# LooSensorNodeV2.net
KiCad netlist of a schematic drawn in EAGLE
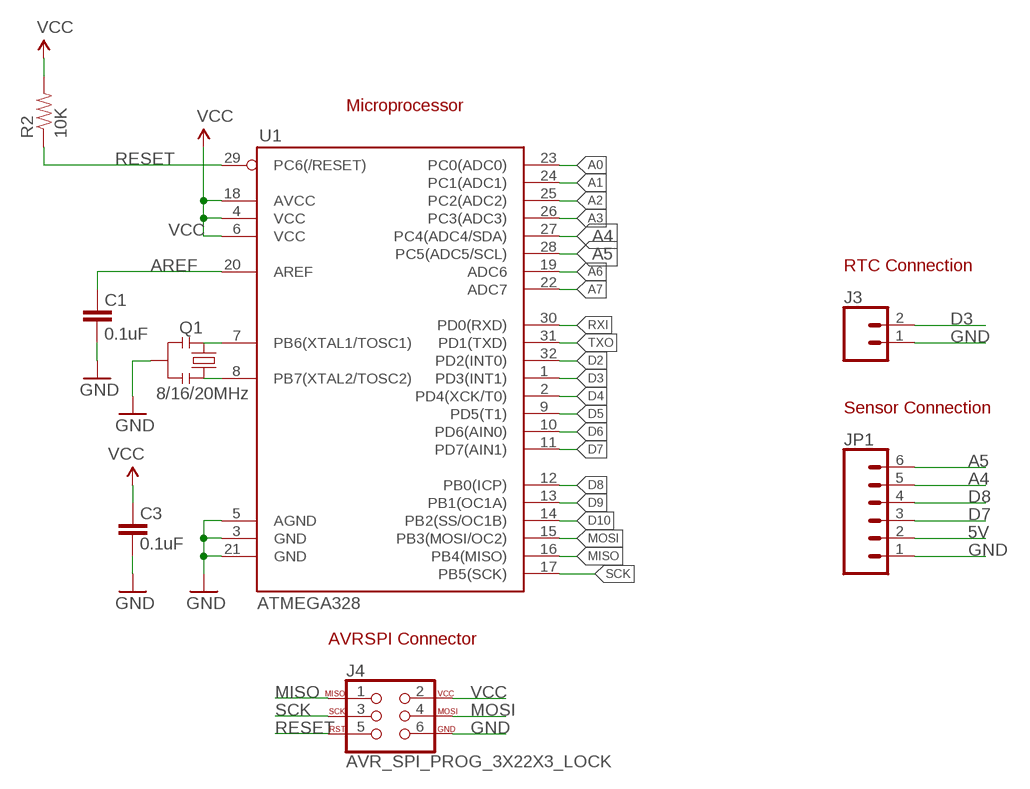
[diagram p0: schematic, sheet 1]
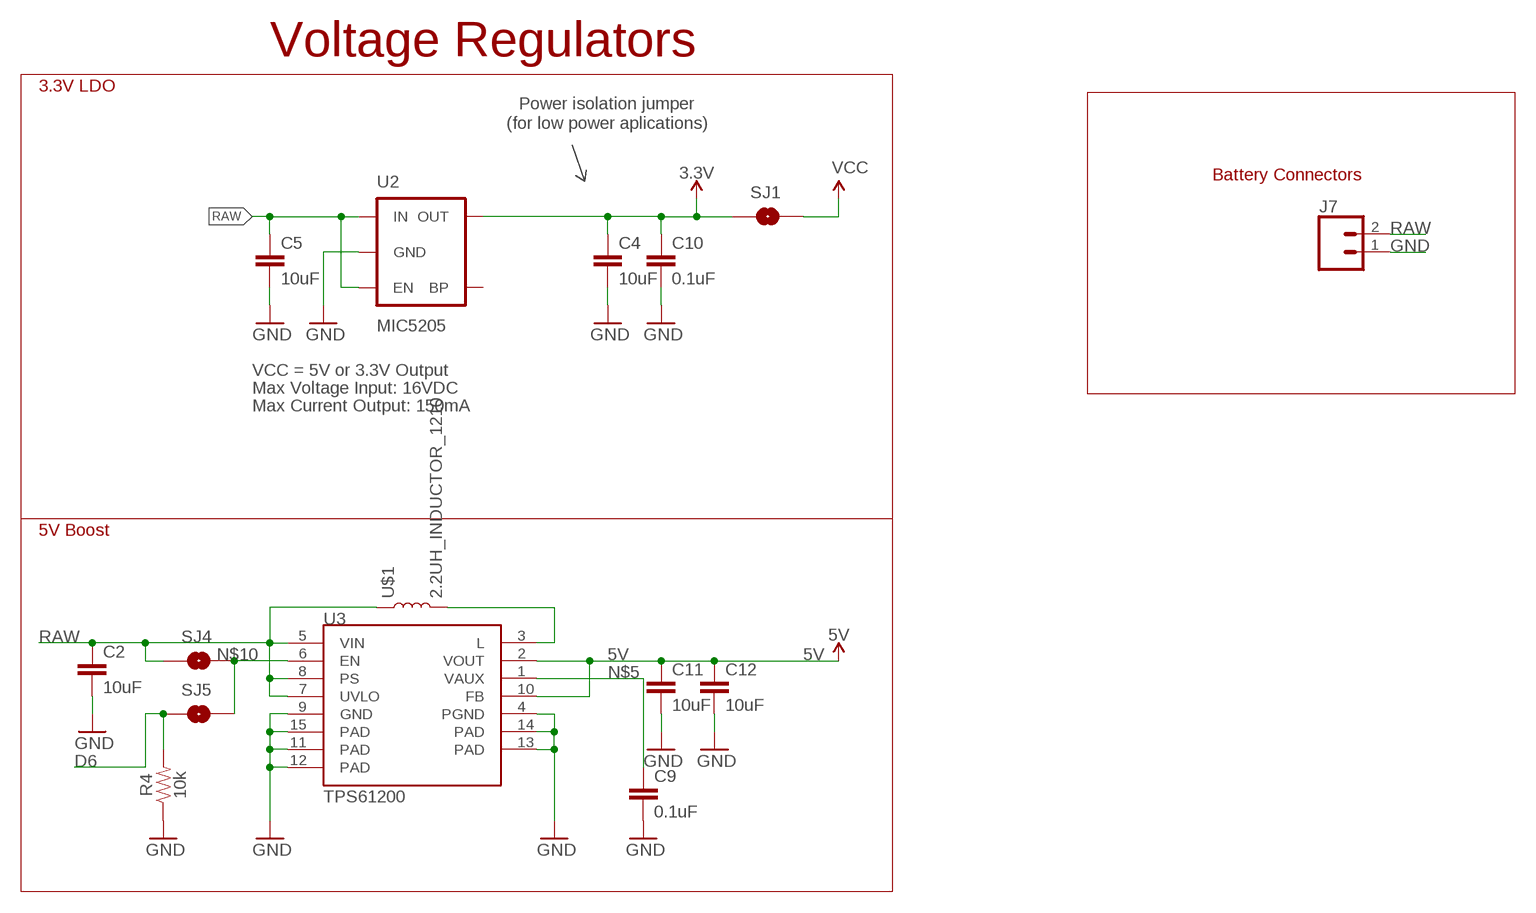
[diagram p1: schematic, sheet 2]
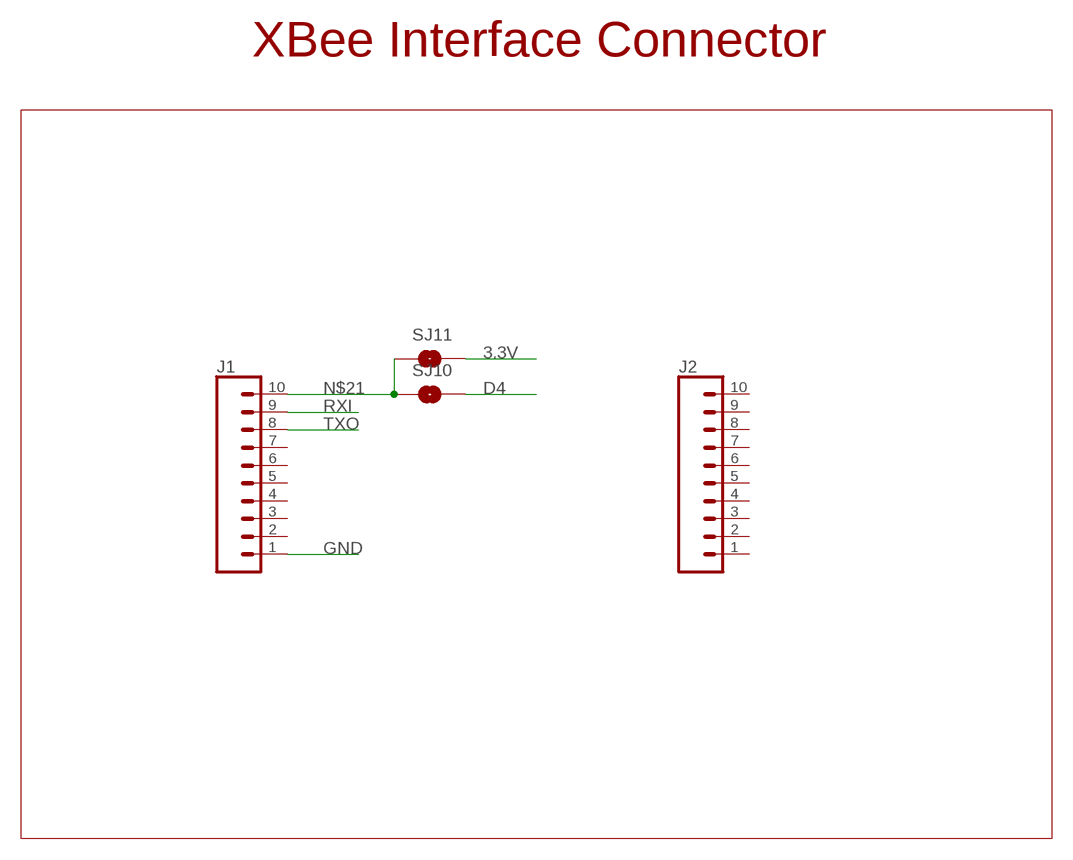
[diagram p2: schematic, sheet 3]

(export (version "E")
  (design (tool "Eeschema 10.0.6"))
  (components
    (comp (ref "C2")
      (value "10uF")
      (footprint "eagle-import:0603")
      (libsource (lib "eagle-import") (part "10UF-0603-6.3V-20%"))
    )
    (comp (ref "C4")
      (value "10uF")
      (footprint "eagle-import:0603")
      (libsource (lib "eagle-import") (part "10UF-0603-6.3V-20%"))
    )
    (comp (ref "C5")
      (value "10uF")
      (footprint "eagle-import:0603")
      (libsource (lib "eagle-import") (part "10UF-0603-6.3V-20%"))
    )
    (comp (ref "C9")
      (value "0.1uF")
      (footprint "eagle-import:0603")
      (libsource (lib "eagle-import") (part "0.1UF-0603-25V-5%"))
    )
    (comp (ref "C10")
      (value "0.1uF")
      (footprint "eagle-import:0603-CAP")
      (libsource (lib "eagle-import") (part "CAP0603-CAP"))
    )
    (comp (ref "C11")
      (value "10uF")
      (footprint "eagle-import:0603")
      (libsource (lib "eagle-import") (part "10UF-0603-6.3V-20%"))
    )
    (comp (ref "C12")
      (value "10uF")
      (footprint "eagle-import:0603")
      (libsource (lib "eagle-import") (part "10UF-0603-6.3V-20%"))
    )
    (comp (ref "J7")
      (value "CONN_02")
      (footprint "eagle-import:1X02")
      (libsource (lib "eagle-import") (part "CONN_02"))
    )
    (comp (ref "R4")
      (value "10k")
      (footprint "eagle-import:0603")
      (libsource (lib "eagle-import") (part "10KOHM-0603-1/10W-1%"))
    )
    (comp (ref "SJ1")
      (value "SOLDERJUMPERNC")
      (footprint "eagle-import:SJ_2S")
      (libsource (lib "eagle-import") (part "SOLDERJUMPERNC"))
    )
    (comp (ref "SJ4")
      (value "SOLDERJUMPERNC")
      (footprint "eagle-import:SJ_2S")
      (libsource (lib "eagle-import") (part "SOLDERJUMPERNC"))
    )
    (comp (ref "SJ5")
      (value "SOLDERJUMPERNC")
      (footprint "eagle-import:SJ_2S")
      (libsource (lib "eagle-import") (part "SOLDERJUMPERNC"))
    )
    (comp (ref "U$1")
      (value "2.2UH_INDUCTOR_1210")
      (footprint "eagle-import:1210")
      (libsource (lib "eagle-import") (part "2.2UH_INDUCTOR_1210"))
    )
    (comp (ref "U2")
      (value "MIC5205")
      (footprint "eagle-import:SOT23-5")
      (libsource (lib "eagle-import") (part "V_REG_LDOSMD"))
    )
    (comp (ref "U3")
      (value "TPS61200")
      (footprint "eagle-import:QFN-10_PAD")
      (libsource (lib "eagle-import") (part "TPS61200"))
    )
    (comp (ref "C1")
      (value "0.1uF")
      (footprint "eagle-import:0603-CAP")
      (libsource (lib "eagle-import") (part "CAP0603-CAP"))
    )
    (comp (ref "C3")
      (value "0.1uF")
      (footprint "eagle-import:0603-CAP")
      (libsource (lib "eagle-import") (part "CAP0603-CAP"))
    )
    (comp (ref "J3")
      (value "CONN_02")
      (footprint "eagle-import:1X02")
      (libsource (lib "eagle-import") (part "CONN_02"))
    )
    (comp (ref "J4")
      (value "AVR_SPI_PROG_3X22X3_LOCK")
      (footprint "eagle-import:2X3_LOCK")
      (libsource (lib "eagle-import") (part "AVR_SPI_PROG_3X22X3_LOCK"))
    )
    (comp (ref "JP1")
      (value "CONN_06SILK_FEMALE_PTH")
      (footprint "eagle-import:1X06")
      (libsource (lib "eagle-import") (part "CONN_06SILK_FEMALE_PTH"))
    )
    (comp (ref "Q1")
      (value "8/16/20MHz")
      (footprint "eagle-import:RESONATOR-SMD-1_1")
      (libsource (lib "eagle-import") (part "RESONATOR1{colon}1"))
    )
    (comp (ref "R2")
      (value "10K")
      (footprint "eagle-import:0603-RES")
      (libsource (lib "eagle-import") (part "RESISTOR0603-RES"))
    )
    (comp (ref "U1")
      (value "ATMEGA328")
      (footprint "eagle-import:TQFP32-08")
      (libsource (lib "eagle-import") (part "ATMEGA168"))
    )
    (comp (ref "J1")
      (value "CONN_102MM")
      (footprint "eagle-import:1X10-2MM")
      (libsource (lib "eagle-import") (part "CONN_102MM"))
    )
    (comp (ref "J2")
      (value "CONN_102MM")
      (footprint "eagle-import:1X10-2MM")
      (libsource (lib "eagle-import") (part "CONN_102MM"))
    )
    (comp (ref "SJ10")
      (value "SOLDERJUMPERNC")
      (footprint "eagle-import:SJ_2S")
      (libsource (lib "eagle-import") (part "SOLDERJUMPERNC"))
    )
    (comp (ref "SJ11")
      (value "SOLDERJUMPERNC")
      (footprint "eagle-import:SJ_2S")
      (libsource (lib "eagle-import") (part "SOLDERJUMPERNC"))
    )
  )
  (nets
    (net (code "1") (name "3.3V") (class "Default")
      (node (ref "C10") (pin "1") (pinfunction "1_1") (pintype "passive"))
      (node (ref "C4") (pin "1") (pinfunction "1_1") (pintype "passive"))
      (node (ref "SJ1") (pin "1") (pinfunction "1_1") (pintype "passive"))
      (node (ref "SJ11") (pin "2") (pinfunction "2_2") (pintype "passive"))
      (node (ref "U2") (pin "5") (pinfunction "OUT_5") (pintype "passive"))
    )
    (net (code "2") (name "5V") (class "Default")
      (node (ref "C11") (pin "1") (pinfunction "1_1") (pintype "passive"))
      (node (ref "C12") (pin "1") (pinfunction "1_1") (pintype "passive"))
      (node (ref "JP1") (pin "2") (pinfunction "2_2") (pintype "passive"))
      (node (ref "U3") (pin "10") (pinfunction "FB_10") (pintype "passive"))
      (node (ref "U3") (pin "2") (pinfunction "VOUT_2") (pintype "passive"))
    )
    (net (code "3") (name "A0") (class "Default")
      (node (ref "U1") (pin "23") (pinfunction "PC0(ADC0)_23") (pintype "bidirectional"))
    )
    (net (code "4") (name "A1") (class "Default")
      (node (ref "U1") (pin "24") (pinfunction "PC1(ADC1)_24") (pintype "bidirectional"))
    )
    (net (code "5") (name "A2") (class "Default")
      (node (ref "U1") (pin "25") (pinfunction "PC2(ADC2)_25") (pintype "bidirectional"))
    )
    (net (code "6") (name "A3") (class "Default")
      (node (ref "U1") (pin "26") (pinfunction "PC3(ADC3)_26") (pintype "bidirectional"))
    )
    (net (code "7") (name "A4") (class "Default")
      (node (ref "JP1") (pin "5") (pinfunction "5_5") (pintype "passive"))
      (node (ref "U1") (pin "27") (pinfunction "PC4(ADC4/SDA)_27") (pintype "bidirectional"))
    )
    (net (code "8") (name "A5") (class "Default")
      (node (ref "JP1") (pin "6") (pinfunction "6_6") (pintype "passive"))
      (node (ref "U1") (pin "28") (pinfunction "PC5(ADC5/SCL)_28") (pintype "bidirectional"))
    )
    (net (code "9") (name "A6") (class "Default")
      (node (ref "U1") (pin "19") (pinfunction "ADC6_19") (pintype "bidirectional"))
    )
    (net (code "10") (name "A7") (class "Default")
      (node (ref "U1") (pin "22") (pinfunction "ADC7_22") (pintype "bidirectional"))
    )
    (net (code "11") (name "AREF") (class "Default")
      (node (ref "C1") (pin "2") (pinfunction "2_2") (pintype "passive"))
      (node (ref "U1") (pin "20") (pinfunction "AREF_20") (pintype "bidirectional"))
    )
    (net (code "12") (name "D2") (class "Default")
      (node (ref "U1") (pin "32") (pinfunction "PD2(INT0)_32") (pintype "bidirectional"))
    )
    (net (code "13") (name "D3") (class "Default")
      (node (ref "J3") (pin "2") (pinfunction "2_2") (pintype "passive"))
      (node (ref "U1") (pin "1") (pinfunction "PD3(INT1)_1") (pintype "bidirectional"))
    )
    (net (code "14") (name "D4") (class "Default")
      (node (ref "SJ10") (pin "2") (pinfunction "2_2") (pintype "passive"))
      (node (ref "U1") (pin "2") (pinfunction "PD4(XCK/T0)_2") (pintype "bidirectional"))
    )
    (net (code "15") (name "D5") (class "Default")
      (node (ref "U1") (pin "9") (pinfunction "PD5(T1)_9") (pintype "bidirectional"))
    )
    (net (code "16") (name "D6") (class "Default")
      (node (ref "R4") (pin "2") (pinfunction "2_2") (pintype "passive"))
      (node (ref "SJ5") (pin "1") (pinfunction "1_1") (pintype "passive"))
      (node (ref "U1") (pin "10") (pinfunction "PD6(AIN0)_10") (pintype "bidirectional"))
    )
    (net (code "17") (name "D7") (class "Default")
      (node (ref "JP1") (pin "3") (pinfunction "3_3") (pintype "passive"))
      (node (ref "U1") (pin "11") (pinfunction "PD7(AIN1)_11") (pintype "bidirectional"))
    )
    (net (code "18") (name "D8") (class "Default")
      (node (ref "JP1") (pin "4") (pinfunction "4_4") (pintype "passive"))
      (node (ref "U1") (pin "12") (pinfunction "PB0(ICP)_12") (pintype "bidirectional"))
    )
    (net (code "19") (name "D9") (class "Default")
      (node (ref "U1") (pin "13") (pinfunction "PB1(OC1A)_13") (pintype "bidirectional"))
    )
    (net (code "20") (name "D10") (class "Default")
      (node (ref "U1") (pin "14") (pinfunction "PB2(SS/OC1B)_14") (pintype "bidirectional"))
    )
    (net (code "21") (name "GND") (class "Default")
      (node (ref "C1") (pin "1") (pinfunction "1_1") (pintype "passive"))
      (node (ref "C10") (pin "2") (pinfunction "2_2") (pintype "passive"))
      (node (ref "C11") (pin "2") (pinfunction "2_2") (pintype "passive"))
      (node (ref "C12") (pin "2") (pinfunction "2_2") (pintype "passive"))
      (node (ref "C2") (pin "2") (pinfunction "2_2") (pintype "passive"))
      (node (ref "C3") (pin "1") (pinfunction "1_1") (pintype "passive"))
      (node (ref "C4") (pin "2") (pinfunction "2_2") (pintype "passive"))
      (node (ref "C5") (pin "2") (pinfunction "2_2") (pintype "passive"))
      (node (ref "C9") (pin "2") (pinfunction "2_2") (pintype "passive"))
      (node (ref "J1") (pin "1") (pinfunction "1_1") (pintype "passive"))
      (node (ref "J3") (pin "1") (pinfunction "1_1") (pintype "passive"))
      (node (ref "J4") (pin "6") (pinfunction "6_6") (pintype "passive"))
      (node (ref "J7") (pin "1") (pinfunction "1_1") (pintype "passive"))
      (node (ref "JP1") (pin "1") (pinfunction "1_1") (pintype "passive"))
      (node (ref "Q1") (pin "2") (pinfunction "2_2") (pintype "passive"))
      (node (ref "R4") (pin "1") (pinfunction "1_1") (pintype "passive"))
      (node (ref "U1") (pin "21") (pinfunction "GND_21") (pintype "bidirectional"))
      (node (ref "U1") (pin "3") (pinfunction "GND_3") (pintype "bidirectional"))
      (node (ref "U1") (pin "5") (pinfunction "AGND_5") (pintype "bidirectional"))
      (node (ref "U2") (pin "2") (pinfunction "GND_2") (pintype "input"))
      (node (ref "U3") (pin "11") (pinfunction "PAD_11") (pintype "power_in"))
      (node (ref "U3") (pin "12") (pinfunction "PAD_12") (pintype "power_in"))
      (node (ref "U3") (pin "13") (pinfunction "PAD_13") (pintype "power_in"))
      (node (ref "U3") (pin "14") (pinfunction "PAD_14") (pintype "power_in"))
      (node (ref "U3") (pin "15") (pinfunction "PAD_15") (pintype "power_in"))
      (node (ref "U3") (pin "4") (pinfunction "PGND_4") (pintype "power_in"))
      (node (ref "U3") (pin "9") (pinfunction "GND_9") (pintype "power_in"))
    )
    (net (code "22") (name "MISO") (class "Default")
      (node (ref "J4") (pin "1") (pinfunction "1_1") (pintype "passive"))
      (node (ref "U1") (pin "16") (pinfunction "PB4(MISO)_16") (pintype "bidirectional"))
    )
    (net (code "23") (name "MOSI") (class "Default")
      (node (ref "J4") (pin "4") (pinfunction "4_4") (pintype "passive"))
      (node (ref "U1") (pin "15") (pinfunction "PB3(MOSI/OC2)_15") (pintype "bidirectional"))
    )
    (net (code "24") (name "N$5") (class "Default")
      (node (ref "C9") (pin "1") (pinfunction "1_1") (pintype "passive"))
      (node (ref "U3") (pin "1") (pinfunction "VAUX_1") (pintype "passive"))
    )
    (net (code "25") (name "N$10") (class "Default")
      (node (ref "SJ4") (pin "2") (pinfunction "2_2") (pintype "passive"))
      (node (ref "SJ5") (pin "2") (pinfunction "2_2") (pintype "passive"))
      (node (ref "U3") (pin "6") (pinfunction "EN_6") (pintype "input"))
    )
    (net (code "26") (name "N$21") (class "Default")
      (node (ref "J1") (pin "10") (pinfunction "10_10") (pintype "passive"))
      (node (ref "SJ10") (pin "1") (pinfunction "1_1") (pintype "passive"))
      (node (ref "SJ11") (pin "1") (pinfunction "1_1") (pintype "passive"))
    )
    (net (code "27") (name "Net-(U1-PB6(XTAL1{slash}TOSC1))") (class "Default")
      (node (ref "Q1") (pin "1") (pinfunction "1_1") (pintype "passive"))
      (node (ref "U1") (pin "7") (pinfunction "PB6(XTAL1/TOSC1)_7") (pintype "bidirectional"))
    )
    (net (code "28") (name "Net-(U1-PB7(XTAL2{slash}TOSC2))") (class "Default")
      (node (ref "Q1") (pin "3") (pinfunction "3_3") (pintype "passive"))
      (node (ref "U1") (pin "8") (pinfunction "PB7(XTAL2/TOSC2)_8") (pintype "bidirectional"))
    )
    (net (code "29") (name "Net-(U3-L)") (class "Default")
      (node (ref "U$1") (pin "2") (pinfunction "2_2") (pintype "passive"))
      (node (ref "U3") (pin "3") (pinfunction "L_3") (pintype "passive"))
    )
    (net (code "30") (name "RAW") (class "Default")
      (node (ref "C2") (pin "1") (pinfunction "1_1") (pintype "passive"))
      (node (ref "C5") (pin "1") (pinfunction "1_1") (pintype "passive"))
      (node (ref "J7") (pin "2") (pinfunction "2_2") (pintype "passive"))
      (node (ref "SJ4") (pin "1") (pinfunction "1_1") (pintype "passive"))
      (node (ref "U$1") (pin "1") (pinfunction "1_1") (pintype "passive"))
      (node (ref "U2") (pin "1") (pinfunction "IN_1") (pintype "input"))
      (node (ref "U2") (pin "3") (pinfunction "EN_3") (pintype "input"))
      (node (ref "U3") (pin "5") (pinfunction "VIN_5") (pintype "power_in"))
      (node (ref "U3") (pin "7") (pinfunction "UVLO_7") (pintype "passive"))
      (node (ref "U3") (pin "8") (pinfunction "PS_8") (pintype "input"))
    )
    (net (code "31") (name "RESET") (class "Default")
      (node (ref "J4") (pin "5") (pinfunction "5_5") (pintype "passive"))
      (node (ref "R2") (pin "1") (pinfunction "1_1") (pintype "passive"))
      (node (ref "U1") (pin "29") (pinfunction "PC6(/RESET)_29") (pintype "bidirectional"))
    )
    (net (code "32") (name "RXI") (class "Default")
      (node (ref "J1") (pin "9") (pinfunction "9_9") (pintype "passive"))
      (node (ref "U1") (pin "30") (pinfunction "PD0(RXD)_30") (pintype "bidirectional"))
    )
    (net (code "33") (name "SCK") (class "Default")
      (node (ref "J4") (pin "3") (pinfunction "3_3") (pintype "passive"))
      (node (ref "U1") (pin "17") (pinfunction "PB5(SCK)_17") (pintype "bidirectional"))
    )
    (net (code "34") (name "TXO") (class "Default")
      (node (ref "J1") (pin "8") (pinfunction "8_8") (pintype "passive"))
      (node (ref "U1") (pin "31") (pinfunction "PD1(TXD)_31") (pintype "bidirectional"))
    )
    (net (code "35") (name "VCC") (class "Default")
      (node (ref "C3") (pin "2") (pinfunction "2_2") (pintype "passive"))
      (node (ref "J4") (pin "2") (pinfunction "2_2") (pintype "passive"))
      (node (ref "R2") (pin "2") (pinfunction "2_2") (pintype "passive"))
      (node (ref "SJ1") (pin "2") (pinfunction "2_2") (pintype "passive"))
      (node (ref "U1") (pin "18") (pinfunction "AVCC_18") (pintype "bidirectional"))
      (node (ref "U1") (pin "4") (pinfunction "VCC_4") (pintype "bidirectional"))
      (node (ref "U1") (pin "6") (pinfunction "VCC_6") (pintype "bidirectional"))
    )
    (net (code "36") (name "unconnected-(J1-Pad2)") (class "Default")
      (node (ref "J1") (pin "2") (pinfunction "2_2") (pintype "passive"))
    )
    (net (code "37") (name "unconnected-(J1-Pad3)") (class "Default")
      (node (ref "J1") (pin "3") (pinfunction "3_3") (pintype "passive"))
    )
    (net (code "38") (name "unconnected-(J1-Pad4)") (class "Default")
      (node (ref "J1") (pin "4") (pinfunction "4_4") (pintype "passive"))
    )
    (net (code "39") (name "unconnected-(J1-Pad5)") (class "Default")
      (node (ref "J1") (pin "5") (pinfunction "5_5") (pintype "passive"))
    )
    (net (code "40") (name "unconnected-(J1-Pad6)") (class "Default")
      (node (ref "J1") (pin "6") (pinfunction "6_6") (pintype "passive"))
    )
    (net (code "41") (name "unconnected-(J1-Pad7)") (class "Default")
      (node (ref "J1") (pin "7") (pinfunction "7_7") (pintype "passive"))
    )
    (net (code "42") (name "unconnected-(J2-Pad1)") (class "Default")
      (node (ref "J2") (pin "1") (pinfunction "1_1") (pintype "passive"))
    )
    (net (code "43") (name "unconnected-(J2-Pad2)") (class "Default")
      (node (ref "J2") (pin "2") (pinfunction "2_2") (pintype "passive"))
    )
    (net (code "44") (name "unconnected-(J2-Pad3)") (class "Default")
      (node (ref "J2") (pin "3") (pinfunction "3_3") (pintype "passive"))
    )
    (net (code "45") (name "unconnected-(J2-Pad4)") (class "Default")
      (node (ref "J2") (pin "4") (pinfunction "4_4") (pintype "passive"))
    )
    (net (code "46") (name "unconnected-(J2-Pad5)") (class "Default")
      (node (ref "J2") (pin "5") (pinfunction "5_5") (pintype "passive"))
    )
    (net (code "47") (name "unconnected-(J2-Pad6)") (class "Default")
      (node (ref "J2") (pin "6") (pinfunction "6_6") (pintype "passive"))
    )
    (net (code "48") (name "unconnected-(J2-Pad7)") (class "Default")
      (node (ref "J2") (pin "7") (pinfunction "7_7") (pintype "passive"))
    )
    (net (code "49") (name "unconnected-(J2-Pad8)") (class "Default")
      (node (ref "J2") (pin "8") (pinfunction "8_8") (pintype "passive"))
    )
    (net (code "50") (name "unconnected-(J2-Pad9)") (class "Default")
      (node (ref "J2") (pin "9") (pinfunction "9_9") (pintype "passive"))
    )
    (net (code "51") (name "unconnected-(J2-Pad10)") (class "Default")
      (node (ref "J2") (pin "10") (pinfunction "10_10") (pintype "passive"))
    )
    (net (code "52") (name "unconnected-(U2-BP-Pad4)") (class "Default")
      (node (ref "U2") (pin "4") (pinfunction "BP_4") (pintype "input"))
    )
  )
)
